# RTC.net
KiCad netlist of a schematic drawn in Altium Designer
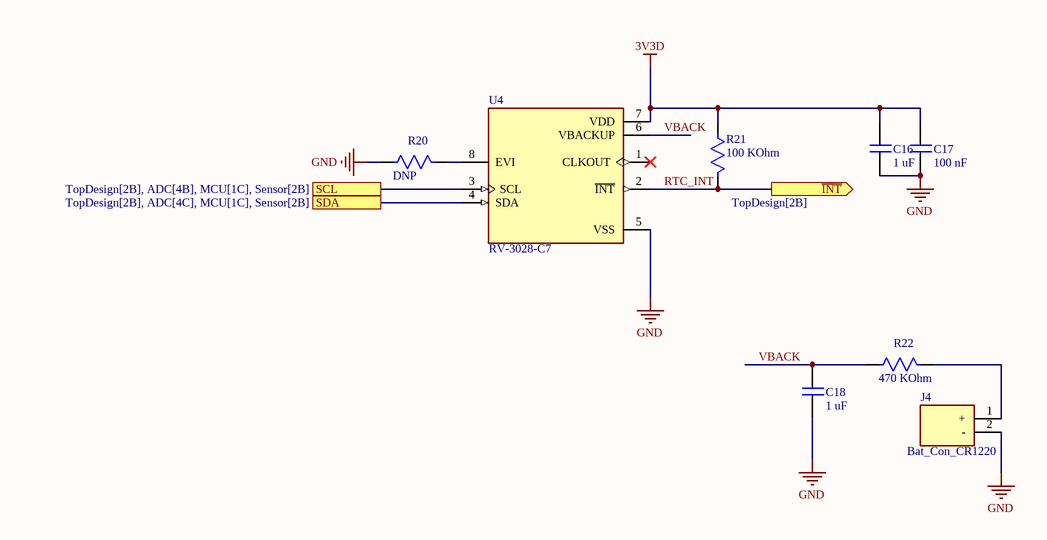
[diagram p0: RTC.SchDoc]

(export (version "E")
  (design (tool "Eeschema 10.0.6"))
  (components
    (comp (ref "C16")
      (value "1 uF")
      (footprint "CAP_0603")
      (description "Cap SMD.")
      (libsource (lib "Aptinex_discrete") (part "Cap SMD"))
    )
    (comp (ref "C17")
      (value "100 nF")
      (footprint "CAP_0603")
      (description "Cap SMD.")
      (libsource (lib "Aptinex_discrete") (part "Cap SMD"))
    )
    (comp (ref "C18")
      (value "1 uF")
      (footprint "CAP_0603")
      (description "Cap SMD.")
      (libsource (lib "Aptinex_discrete") (part "Cap SMD"))
    )
    (comp (ref "J4")
      (value "Bat_Con_CR1220")
      (footprint "Bat_Con_CR1220")
      (description "Connector")
      (fields
        (field (name "MANUFACTURER_PART_NUMBER") "S8411-45R")
        (field (name "MOUSER PART NUMBER") "855-S8411-45R")
      )
      (libsource (lib "Aptinex_connectors") (part "Bat_Con_CR1220"))
    )
    (comp (ref "R20")
      (value "DNP")
      (footprint "RES_0402")
      (description "SMD Resistor")
      (fields (field (name "MP") "RC0805FR-07330RL") (field (name "MF") "Yageo"))
      (libsource (lib "Aptinex_discrete") (part "Res smd"))
    )
    (comp (ref "R21")
      (value "100 KOhm")
      (footprint "Res_0603")
      (description "SMD Resistor")
      (fields (field (name "MP") "RC0805FR-07330RL") (field (name "MF") "Yageo"))
      (libsource (lib "Aptinex_discrete") (part "Res smd"))
    )
    (comp (ref "R22")
      (value "470 KOhm")
      (footprint "Res_0603")
      (description "SMD Resistor")
      (fields (field (name "MP") "RC0805FR-07330RL") (field (name "MF") "Yageo"))
      (libsource (lib "Aptinex_discrete") (part "Res smd"))
    )
    (comp (ref "U4")
      (value "RV-3028-C7")
      (footprint "IC_RV-3028-C7")
      (description "Real Time Clock (RTC) IC Clock/Calendar 2B, 43B IÂ²C, 2-Wire Serial 8-WCDFN")
      (fields (field (name "MF") "Micro Crystal"))
      (libsource (lib "Aptinex_devices") (part "RV-3028-C7"))
    )
  )
  (nets
    (net (code "1") (name "/RTC_INT") (class "Default")
      (node (ref "R21") (pin "1") (pinfunction "1_1") (pintype "passive"))
      (node (ref "U4") (pin "2") (pinfunction "~{INT}_2") (pintype "output"))
    )
    (net (code "2") (name "/SCL") (class "Default")
      (node (ref "U4") (pin "3") (pinfunction "SCL_3") (pintype "input"))
    )
    (net (code "3") (name "/SDA") (class "Default")
      (node (ref "U4") (pin "4") (pinfunction "SDA_4") (pintype "input"))
    )
    (net (code "4") (name "/VBACK") (class "Default")
      (node (ref "C18") (pin "2") (pinfunction "2_2") (pintype "passive"))
      (node (ref "R22") (pin "2") (pinfunction "2_2") (pintype "passive"))
      (node (ref "U4") (pin "6") (pinfunction "VBACKUP_6") (pintype "power_in"))
    )
    (net (code "5") (name "3V3D") (class "Default")
      (node (ref "C16") (pin "2") (pinfunction "2_2") (pintype "passive"))
      (node (ref "C17") (pin "2") (pinfunction "2_2") (pintype "passive"))
      (node (ref "R21") (pin "2") (pinfunction "2_2") (pintype "passive"))
      (node (ref "U4") (pin "7") (pinfunction "VDD_7") (pintype "power_in"))
    )
    (net (code "6") (name "GND") (class "Default")
      (node (ref "C16") (pin "1") (pinfunction "1_1") (pintype "passive"))
      (node (ref "C17") (pin "1") (pinfunction "1_1") (pintype "passive"))
      (node (ref "C18") (pin "1") (pinfunction "1_1") (pintype "passive"))
      (node (ref "J4") (pin "2") (pinfunction "-_2") (pintype "passive"))
      (node (ref "R20") (pin "2") (pinfunction "2_2") (pintype "passive"))
      (node (ref "U4") (pin "5") (pinfunction "VSS_5") (pintype "power_in"))
    )
    (net (code "7") (name "Net-(J4-+)") (class "Default")
      (node (ref "J4") (pin "1") (pinfunction "+_1") (pintype "passive"))
      (node (ref "R22") (pin "1") (pinfunction "1_1") (pintype "passive"))
    )
    (net (code "8") (name "Net-(U4-EVI)") (class "Default")
      (node (ref "R20") (pin "1") (pinfunction "1_1") (pintype "passive"))
      (node (ref "U4") (pin "8") (pinfunction "EVI_8") (pintype "passive"))
    )
    (net (code "9") (name "unconnected-(U4-CLKOUT-Pad1)") (class "Default")
      (node (ref "U4") (pin "1") (pinfunction "CLKOUT_1") (pintype "output+no_connect"))
    )
  )
)
